# ftdi.net
KiCad netlist of a schematic drawn in Altium Designer
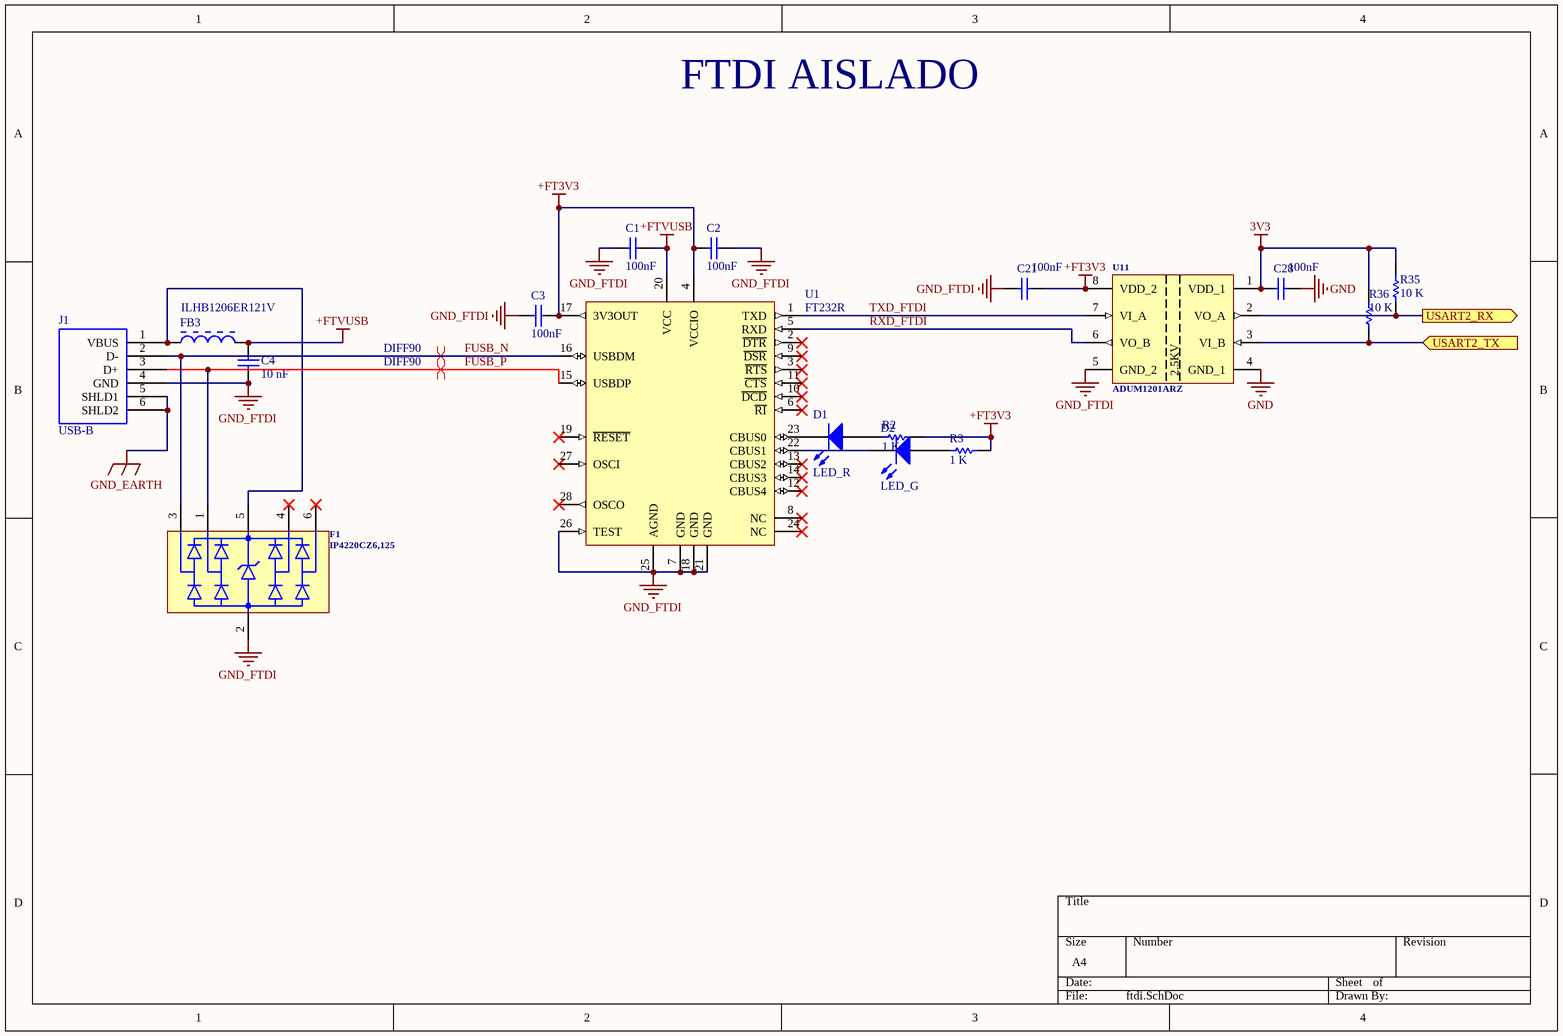
[diagram p0: ftdi.SchDoc]

(export (version "E")
  (design (tool "Eeschema 10.0.6"))
  (components
    (comp (ref "C1")
      (value "100nF")
      (footprint "0603")
      (description "Capacitor")
      (fields (field (name "PUBLISHER") "Altium Limited"))
      (libsource (lib "sallen") (part "cond"))
    )
    (comp (ref "C2")
      (value "100nF")
      (footprint "0603")
      (description "Capacitor")
      (fields (field (name "PUBLISHER") "Altium Limited"))
      (libsource (lib "sallen") (part "cond"))
    )
    (comp (ref "C3")
      (value "100nF")
      (footprint "0603")
      (description "Capacitor")
      (fields (field (name "PUBLISHER") "Altium Limited"))
      (libsource (lib "sallen") (part "cond"))
    )
    (comp (ref "C4")
      (value "10 nF")
      (footprint "0603")
      (description "Capacitor")
      (fields (field (name "PUBLISHER") "Altium Limited"))
      (libsource (lib "sallen") (part "cond"))
    )
    (comp (ref "C21")
      (value "100nF")
      (footprint "0603")
      (description "Capacitor")
      (fields (field (name "PUBLISHER") "Altium Limited"))
      (libsource (lib "sallen") (part "cond"))
    )
    (comp (ref "C28")
      (value "100nF")
      (footprint "0603")
      (description "Capacitor")
      (fields (field (name "PUBLISHER") "Altium Limited"))
      (libsource (lib "sallen") (part "cond"))
    )
    (comp (ref "D1")
      (value "LED_R")
      (footprint "LED0603R")
      (description "Typical RED, GREEN, YELLOW, AMBER GaAs LED")
      (fields (field (name "PUBLISHER") "Altium Limited"))
      (libsource (lib "sallen") (part "diodo_led"))
    )
    (comp (ref "D2")
      (value "LED_G")
      (footprint "LED0603G")
      (description "Typical RED, GREEN, YELLOW, AMBER GaAs LED")
      (fields (field (name "PUBLISHER") "Altium Limited"))
      (libsource (lib "sallen") (part "diodo_led"))
    )
    (comp (ref "F1")
      (value "IP4220CZ6,125")
      (footprint "SOT26A-6N")
      (description "USB DUAL ESD PROTECT 6TSOP")
      (libsource (lib "HSDS_2.0") (part "IP4220CZ6,125"))
    )
    (comp (ref "FB3") (value "ILHB1206ER121V") (footprint "1206") (libsource (lib "sallen") (part "FERRITA")))
    (comp (ref "J1") (value "USB-B") (footprint "USB-B_292304-1") (libsource (lib "sallen") (part "USB-B")))
    (comp (ref "R2")
      (value "1 K")
      (footprint "R0603")
      (description "Resistor")
      (fields (field (name "PUBLISHER") "Altium Limited"))
      (libsource (lib "sallen") (part "res1"))
    )
    (comp (ref "R3")
      (value "1 K")
      (footprint "R0603")
      (description "Resistor")
      (fields (field (name "PUBLISHER") "Altium Limited"))
      (libsource (lib "sallen") (part "res1"))
    )
    (comp (ref "R35")
      (value "10 K")
      (footprint "R0603")
      (description "Resistor")
      (fields (field (name "PUBLISHER") "Altium Limited"))
      (libsource (lib "sallen") (part "res1"))
    )
    (comp (ref "R36")
      (value "10 K")
      (footprint "R0603")
      (description "Resistor")
      (fields (field (name "PUBLISHER") "Altium Limited"))
      (libsource (lib "sallen") (part "res1"))
    )
    (comp (ref "U1")
      (value "FT232R")
      (footprint "FT232RL_SSOP-28_L")
      (description "USB UART Asynchronous Serial Data Transfer Chip, 28-pin SSOP, Tape and Reel")
      (fields (field (name "PARTNUMBER") "FT232RL-Reel") (field (name "MANUFACTURER") "FTDI"))
      (libsource (lib "sallen") (part "FT232R"))
    )
    (comp (ref "U11")
      (value "ADUM1201ARZ")
      (footprint "SOIC127P600-8AN")
      (description "ISOLAT DGTL 2.5KVrms 1Mbps 2CH 8-SOIC")
      (libsource (lib "sallen_sim") (part "ADUM1201ARZ"))
    )
  )
  (nets
    (net (code "1") (name "+FT3V3") (class "Default")
      (node (ref "C2") (pin "1") (pinfunction "1_1") (pintype "passive"))
      (node (ref "C21") (pin "2") (pinfunction "2_2") (pintype "passive"))
      (node (ref "C3") (pin "2") (pinfunction "2_2") (pintype "passive"))
      (node (ref "R2") (pin "2") (pinfunction "2_2") (pintype "passive"))
      (node (ref "R3") (pin "2") (pinfunction "2_2") (pintype "passive"))
      (node (ref "U1") (pin "17") (pinfunction "3V3OUT_17") (pintype "output"))
      (node (ref "U1") (pin "4") (pinfunction "VCCIO_4") (pintype "power_in"))
      (node (ref "U11") (pin "8") (pinfunction "VDD_2_8") (pintype "power_in"))
    )
    (net (code "2") (name "+FTVUSB") (class "Default")
      (node (ref "C1") (pin "2") (pinfunction "2_2") (pintype "passive"))
      (node (ref "C4") (pin "2") (pinfunction "2_2") (pintype "passive"))
      (node (ref "FB3") (pin "2") (pinfunction "2_2") (pintype "passive"))
      (node (ref "U1") (pin "20") (pinfunction "VCC_20") (pintype "power_in"))
    )
    (net (code "3") (name "/FUSB_N") (class "Default")
      (node (ref "F1") (pin "3") (pinfunction "3_3") (pintype "passive"))
      (node (ref "J1") (pin "2") (pinfunction "D-_2") (pintype "passive"))
      (node (ref "U1") (pin "16") (pinfunction "USBDM_16") (pintype "bidirectional"))
    )
    (net (code "4") (name "/FUSB_P") (class "Default")
      (node (ref "F1") (pin "1") (pinfunction "1_1") (pintype "passive"))
      (node (ref "J1") (pin "3") (pinfunction "D+_3") (pintype "passive"))
      (node (ref "U1") (pin "15") (pinfunction "USBDP_15") (pintype "bidirectional"))
    )
    (net (code "5") (name "/RXD_FTDI") (class "Default")
      (node (ref "U1") (pin "5") (pinfunction "RXD_5") (pintype "input"))
      (node (ref "U11") (pin "6") (pinfunction "VO_B_6") (pintype "output"))
    )
    (net (code "6") (name "/TXD_FTDI") (class "Default")
      (node (ref "U1") (pin "1") (pinfunction "TXD_1") (pintype "output"))
      (node (ref "U11") (pin "7") (pinfunction "VI_A_7") (pintype "input"))
    )
    (net (code "7") (name "/USART2_RX") (class "Default")
      (node (ref "R35") (pin "1") (pinfunction "1_1") (pintype "passive"))
      (node (ref "U11") (pin "2") (pinfunction "VO_A_2") (pintype "output"))
    )
    (net (code "8") (name "/USART2_TX") (class "Default")
      (node (ref "R36") (pin "1") (pinfunction "1_1") (pintype "passive"))
      (node (ref "U11") (pin "3") (pinfunction "VI_B_3") (pintype "input"))
    )
    (net (code "9") (name "3V3") (class "Default")
      (node (ref "C28") (pin "1") (pinfunction "1_1") (pintype "passive"))
      (node (ref "R35") (pin "2") (pinfunction "2_2") (pintype "passive"))
      (node (ref "R36") (pin "2") (pinfunction "2_2") (pintype "passive"))
      (node (ref "U11") (pin "1") (pinfunction "VDD_1_1") (pintype "power_in"))
    )
    (net (code "10") (name "GND") (class "Default")
      (node (ref "C28") (pin "2") (pinfunction "2_2") (pintype "passive"))
      (node (ref "U11") (pin "4") (pinfunction "GND_1_4") (pintype "power_in"))
    )
    (net (code "11") (name "GND_EARTH") (class "Default")
      (node (ref "J1") (pin "5") (pinfunction "SHLD1_5") (pintype "passive"))
      (node (ref "J1") (pin "6") (pinfunction "SHLD2_6") (pintype "passive"))
    )
    (net (code "12") (name "GND_FTDI") (class "Default")
      (node (ref "C1") (pin "1") (pinfunction "1_1") (pintype "passive"))
      (node (ref "C2") (pin "2") (pinfunction "2_2") (pintype "passive"))
      (node (ref "C21") (pin "1") (pinfunction "1_1") (pintype "passive"))
      (node (ref "C3") (pin "1") (pinfunction "1_1") (pintype "passive"))
      (node (ref "C4") (pin "1") (pinfunction "1_1") (pintype "passive"))
      (node (ref "F1") (pin "2") (pinfunction "2_2") (pintype "passive"))
      (node (ref "J1") (pin "4") (pinfunction "GND_4") (pintype "passive"))
      (node (ref "U1") (pin "18") (pinfunction "GND_18") (pintype "power_in"))
      (node (ref "U1") (pin "21") (pinfunction "GND_21") (pintype "power_in"))
      (node (ref "U1") (pin "25") (pinfunction "AGND_25") (pintype "power_in"))
      (node (ref "U1") (pin "26") (pinfunction "TEST_26") (pintype "input"))
      (node (ref "U1") (pin "7") (pinfunction "GND_7") (pintype "power_in"))
      (node (ref "U11") (pin "5") (pinfunction "GND_2_5") (pintype "power_in"))
    )
    (net (code "13") (name "Net-(D1-A)") (class "Default")
      (node (ref "D1") (pin "1") (pinfunction "A_1") (pintype "passive"))
      (node (ref "R2") (pin "1") (pinfunction "1_1") (pintype "passive"))
    )
    (net (code "14") (name "Net-(D1-K)") (class "Default")
      (node (ref "D1") (pin "2") (pinfunction "K_2") (pintype "passive"))
      (node (ref "U1") (pin "23") (pinfunction "CBUS0_23") (pintype "bidirectional"))
    )
    (net (code "15") (name "Net-(D2-A)") (class "Default")
      (node (ref "D2") (pin "1") (pinfunction "A_1") (pintype "passive"))
      (node (ref "R3") (pin "1") (pinfunction "1_1") (pintype "passive"))
    )
    (net (code "16") (name "Net-(D2-K)") (class "Default")
      (node (ref "D2") (pin "2") (pinfunction "K_2") (pintype "passive"))
      (node (ref "U1") (pin "22") (pinfunction "CBUS1_22") (pintype "bidirectional"))
    )
    (net (code "17") (name "Net-(J1-VBUS)") (class "Default")
      (node (ref "F1") (pin "5") (pinfunction "5_5") (pintype "passive"))
      (node (ref "FB3") (pin "1") (pinfunction "1_1") (pintype "passive"))
      (node (ref "J1") (pin "1") (pinfunction "VBUS_1") (pintype "passive"))
    )
    (net (code "18") (name "unconnected-(F1-Pad4)") (class "Default")
      (node (ref "F1") (pin "4") (pinfunction "4_4") (pintype "passive+no_connect"))
    )
    (net (code "19") (name "unconnected-(F1-Pad6)") (class "Default")
      (node (ref "F1") (pin "6") (pinfunction "6_6") (pintype "passive+no_connect"))
    )
    (net (code "20") (name "unconnected-(U1-CBUS2-Pad13)") (class "Default")
      (node (ref "U1") (pin "13") (pinfunction "CBUS2_13") (pintype "bidirectional+no_connect"))
    )
    (net (code "21") (name "unconnected-(U1-CBUS3-Pad14)") (class "Default")
      (node (ref "U1") (pin "14") (pinfunction "CBUS3_14") (pintype "bidirectional+no_connect"))
    )
    (net (code "22") (name "unconnected-(U1-CBUS4-Pad12)") (class "Default")
      (node (ref "U1") (pin "12") (pinfunction "CBUS4_12") (pintype "bidirectional+no_connect"))
    )
    (net (code "23") (name "unconnected-(U1-NC-Pad8)") (class "Default")
      (node (ref "U1") (pin "8") (pinfunction "NC_8") (pintype "passive+no_connect"))
    )
    (net (code "24") (name "unconnected-(U1-NC-Pad24)") (class "Default")
      (node (ref "U1") (pin "24") (pinfunction "NC_24") (pintype "passive+no_connect"))
    )
    (net (code "25") (name "unconnected-(U1-OSCI-Pad27)") (class "Default")
      (node (ref "U1") (pin "27") (pinfunction "OSCI_27") (pintype "input+no_connect"))
    )
    (net (code "26") (name "unconnected-(U1-OSCO-Pad28)") (class "Default")
      (node (ref "U1") (pin "28") (pinfunction "OSCO_28") (pintype "output+no_connect"))
    )
    (net (code "27") (name "unconnected-(U1-~{CTS}-Pad11)") (class "Default")
      (node (ref "U1") (pin "11") (pinfunction "~{CTS}_11") (pintype "input+no_connect"))
    )
    (net (code "28") (name "unconnected-(U1-~{DCD}-Pad10)") (class "Default")
      (node (ref "U1") (pin "10") (pinfunction "~{DCD}_10") (pintype "input+no_connect"))
    )
    (net (code "29") (name "unconnected-(U1-~{DSR}-Pad9)") (class "Default")
      (node (ref "U1") (pin "9") (pinfunction "~{DSR}_9") (pintype "input+no_connect"))
    )
    (net (code "30") (name "unconnected-(U1-~{DTR}-Pad2)") (class "Default")
      (node (ref "U1") (pin "2") (pinfunction "~{DTR}_2") (pintype "output+no_connect"))
    )
    (net (code "31") (name "unconnected-(U1-~{RESET}-Pad19)") (class "Default")
      (node (ref "U1") (pin "19") (pinfunction "~{RESET}_19") (pintype "input+no_connect"))
    )
    (net (code "32") (name "unconnected-(U1-~{RI}-Pad6)") (class "Default")
      (node (ref "U1") (pin "6") (pinfunction "~{RI}_6") (pintype "input+no_connect"))
    )
    (net (code "33") (name "unconnected-(U1-~{RTS}-Pad3)") (class "Default")
      (node (ref "U1") (pin "3") (pinfunction "~{RTS}_3") (pintype "output+no_connect"))
    )
  )
)
